# demuxkd.net
KiCad netlist of a schematic drawn in EAGLE
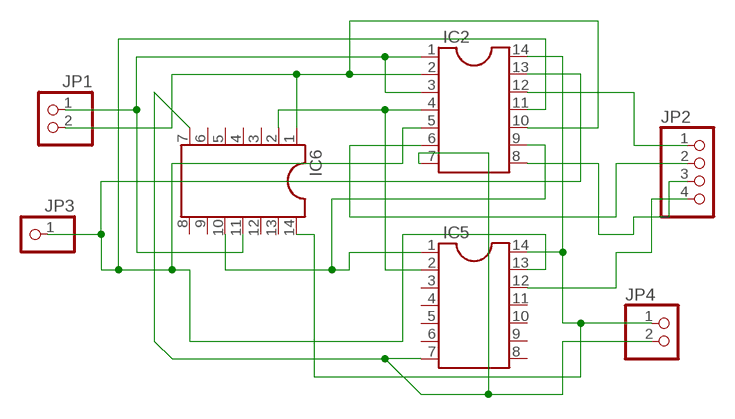
[diagram p0: schematic, sheet 1]

(export (version "E")
  (design (tool "Eeschema 10.0.6"))
  (components
    (comp (ref "IC2")
      (value "DIL14")
      (footprint "eagle-import:DIL14")
      (libsource (lib "eagle-import") (part "DIL14"))
    )
    (comp (ref "IC5")
      (value "DIL14")
      (footprint "eagle-import:DIL14")
      (libsource (lib "eagle-import") (part "DIL14"))
    )
    (comp (ref "IC6")
      (value "DIL14")
      (footprint "eagle-import:DIL14")
      (libsource (lib "eagle-import") (part "DIL14"))
    )
    (comp (ref "JP1")
      (value "PINHD-1X2")
      (footprint "eagle-import:1X02")
      (libsource (lib "eagle-import") (part "PINHD-1X2"))
    )
    (comp (ref "JP2")
      (value "PINHD-1X4")
      (footprint "eagle-import:1X04")
      (libsource (lib "eagle-import") (part "PINHD-1X4"))
    )
    (comp (ref "JP3")
      (value "PINHD-1X1")
      (footprint "eagle-import:1X01")
      (libsource (lib "eagle-import") (part "PINHD-1X1"))
    )
    (comp (ref "JP4")
      (value "PINHD-1X2")
      (footprint "eagle-import:1X02")
      (libsource (lib "eagle-import") (part "PINHD-1X2"))
    )
  )
  (nets
    (net (code "1") (name "Net-(IC2-Pad1)") (class "Default")
      (node (ref "IC2") (pin "1") (pinfunction "1_1") (pintype "passive"))
      (node (ref "IC2") (pin "3") (pinfunction "3_3") (pintype "passive"))
      (node (ref "IC6") (pin "11") (pinfunction "11_11") (pintype "passive"))
      (node (ref "JP1") (pin "1") (pinfunction "1_1") (pintype "passive"))
    )
    (net (code "2") (name "Net-(IC2-Pad4)") (class "Default")
      (node (ref "IC2") (pin "4") (pinfunction "4_4") (pintype "passive"))
      (node (ref "IC5") (pin "2") (pinfunction "2_2") (pintype "passive"))
      (node (ref "IC6") (pin "2") (pinfunction "2_2") (pintype "passive"))
    )
    (net (code "3") (name "Net-(IC2-Pad6)") (class "Default")
      (node (ref "IC2") (pin "6") (pinfunction "6_6") (pintype "passive"))
      (node (ref "JP2") (pin "2") (pinfunction "2_2") (pintype "passive"))
    )
    (net (code "4") (name "Net-(IC2-Pad7)") (class "Default")
      (node (ref "IC2") (pin "7") (pinfunction "7_7") (pintype "passive"))
      (node (ref "IC5") (pin "7") (pinfunction "7_7") (pintype "passive"))
      (node (ref "IC6") (pin "7") (pinfunction "7_7") (pintype "passive"))
      (node (ref "JP4") (pin "2") (pinfunction "2_2") (pintype "passive"))
    )
    (net (code "5") (name "Net-(IC2-Pad8)") (class "Default")
      (node (ref "IC2") (pin "8") (pinfunction "8_8") (pintype "passive"))
      (node (ref "JP2") (pin "3") (pinfunction "3_3") (pintype "passive"))
    )
    (net (code "6") (name "Net-(IC2-Pad9)") (class "Default")
      (node (ref "IC2") (pin "9") (pinfunction "9_9") (pintype "passive"))
      (node (ref "IC5") (pin "1") (pinfunction "1_1") (pintype "passive"))
      (node (ref "IC6") (pin "10") (pinfunction "10_10") (pintype "passive"))
    )
    (net (code "7") (name "Net-(IC2-Pad10)") (class "Default")
      (node (ref "IC2") (pin "10") (pinfunction "10_10") (pintype "passive"))
      (node (ref "IC2") (pin "2") (pinfunction "2_2") (pintype "passive"))
      (node (ref "IC6") (pin "1") (pinfunction "1_1") (pintype "passive"))
      (node (ref "JP1") (pin "2") (pinfunction "2_2") (pintype "passive"))
    )
    (net (code "8") (name "Net-(IC2-Pad11)") (class "Default")
      (node (ref "IC2") (pin "11") (pinfunction "11_11") (pintype "passive"))
      (node (ref "IC2") (pin "13") (pinfunction "13_13") (pintype "passive"))
      (node (ref "IC2") (pin "5") (pinfunction "5_5") (pintype "passive"))
      (node (ref "IC5") (pin "13") (pinfunction "13_13") (pintype "passive"))
      (node (ref "JP3") (pin "1") (pinfunction "1_1") (pintype "passive"))
    )
    (net (code "9") (name "Net-(IC2-Pad12)") (class "Default")
      (node (ref "IC2") (pin "12") (pinfunction "12_12") (pintype "passive"))
      (node (ref "JP2") (pin "1") (pinfunction "1_1") (pintype "passive"))
    )
    (net (code "10") (name "Net-(IC2-Pad14)") (class "Default")
      (node (ref "IC2") (pin "14") (pinfunction "14_14") (pintype "passive"))
      (node (ref "IC5") (pin "14") (pinfunction "14_14") (pintype "passive"))
      (node (ref "IC6") (pin "14") (pinfunction "14_14") (pintype "passive"))
      (node (ref "JP4") (pin "1") (pinfunction "1_1") (pintype "passive"))
    )
    (net (code "11") (name "Net-(IC5-Pad12)") (class "Default")
      (node (ref "IC5") (pin "12") (pinfunction "12_12") (pintype "passive"))
      (node (ref "JP2") (pin "4") (pinfunction "4_4") (pintype "passive"))
    )
    (net (code "12") (name "unconnected-(IC5-Pad3)") (class "Default")
      (node (ref "IC5") (pin "3") (pinfunction "3_3") (pintype "passive"))
    )
    (net (code "13") (name "unconnected-(IC5-Pad4)") (class "Default")
      (node (ref "IC5") (pin "4") (pinfunction "4_4") (pintype "passive"))
    )
    (net (code "14") (name "unconnected-(IC5-Pad5)") (class "Default")
      (node (ref "IC5") (pin "5") (pinfunction "5_5") (pintype "passive"))
    )
    (net (code "15") (name "unconnected-(IC5-Pad6)") (class "Default")
      (node (ref "IC5") (pin "6") (pinfunction "6_6") (pintype "passive"))
    )
    (net (code "16") (name "unconnected-(IC5-Pad8)") (class "Default")
      (node (ref "IC5") (pin "8") (pinfunction "8_8") (pintype "passive"))
    )
    (net (code "17") (name "unconnected-(IC5-Pad9)") (class "Default")
      (node (ref "IC5") (pin "9") (pinfunction "9_9") (pintype "passive"))
    )
    (net (code "18") (name "unconnected-(IC5-Pad10)") (class "Default")
      (node (ref "IC5") (pin "10") (pinfunction "10_10") (pintype "passive"))
    )
    (net (code "19") (name "unconnected-(IC5-Pad11)") (class "Default")
      (node (ref "IC5") (pin "11") (pinfunction "11_11") (pintype "passive"))
    )
    (net (code "20") (name "unconnected-(IC6-Pad3)") (class "Default")
      (node (ref "IC6") (pin "3") (pinfunction "3_3") (pintype "passive"))
    )
    (net (code "21") (name "unconnected-(IC6-Pad4)") (class "Default")
      (node (ref "IC6") (pin "4") (pinfunction "4_4") (pintype "passive"))
    )
    (net (code "22") (name "unconnected-(IC6-Pad5)") (class "Default")
      (node (ref "IC6") (pin "5") (pinfunction "5_5") (pintype "passive"))
    )
    (net (code "23") (name "unconnected-(IC6-Pad6)") (class "Default")
      (node (ref "IC6") (pin "6") (pinfunction "6_6") (pintype "passive"))
    )
    (net (code "24") (name "unconnected-(IC6-Pad8)") (class "Default")
      (node (ref "IC6") (pin "8") (pinfunction "8_8") (pintype "passive"))
    )
    (net (code "25") (name "unconnected-(IC6-Pad9)") (class "Default")
      (node (ref "IC6") (pin "9") (pinfunction "9_9") (pintype "passive"))
    )
    (net (code "26") (name "unconnected-(IC6-Pad12)") (class "Default")
      (node (ref "IC6") (pin "12") (pinfunction "12_12") (pintype "passive"))
    )
    (net (code "27") (name "unconnected-(IC6-Pad13)") (class "Default")
      (node (ref "IC6") (pin "13") (pinfunction "13_13") (pintype "passive"))
    )
  )
)
